# sirius1.net
KiCad netlist of a schematic drawn in EAGLE
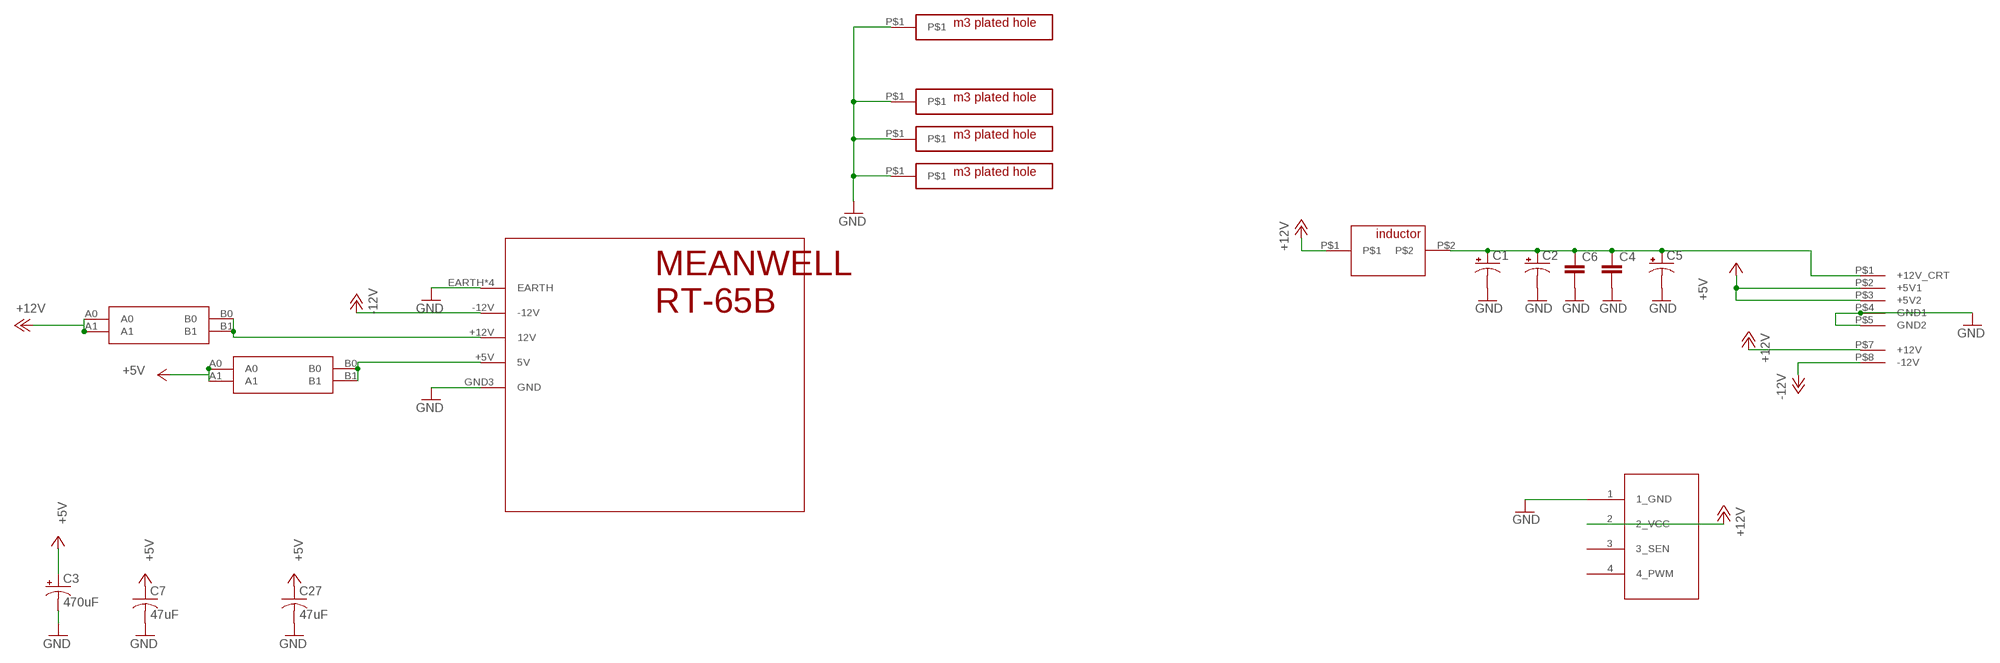
[diagram p0: schematic, sheet 1]

(export (version "E")
  (design (tool "Eeschema 10.0.6"))
  (components
    (comp (ref "C1")
      (value "CPOL-USE3.5-8")
      (footprint "eagle-import:E3,5-8")
      (libsource (lib "eagle-import") (part "CPOL-USE3.5-8"))
    )
    (comp (ref "C2")
      (value "CPOL-USE3.5-8")
      (footprint "eagle-import:E3,5-8")
      (libsource (lib "eagle-import") (part "CPOL-USE3.5-8"))
    )
    (comp (ref "C3")
      (value "470uF")
      (footprint "eagle-import:SMC_D")
      (libsource (lib "eagle-import") (part "CPOL-USSMCD"))
    )
    (comp (ref "C4")
      (value "C5/2.5")
      (footprint "eagle-import:C5B2.5")
      (libsource (lib "eagle-import") (part "C5/2.5"))
    )
    (comp (ref "C5")
      (value "CPOL-USE3.5-8")
      (footprint "eagle-import:E3,5-8")
      (libsource (lib "eagle-import") (part "CPOL-USE3.5-8"))
    )
    (comp (ref "C6")
      (value "C5/2.5")
      (footprint "eagle-import:C5B2.5")
      (libsource (lib "eagle-import") (part "C5/2.5"))
    )
    (comp (ref "C7")
      (value "47uF")
      (footprint "eagle-import:C1210")
      (libsource (lib "eagle-import") (part "C-USC1210"))
    )
    (comp (ref "C27")
      (value "47uF")
      (footprint "eagle-import:C1210")
      (libsource (lib "eagle-import") (part "C-USC1210"))
    )
    (comp (ref "JP4")
      (value "4PIN_FAN")
      (footprint "eagle-import:1X04")
      (libsource (lib "eagle-import") (part "4PIN_FAN"))
    )
    (comp (ref "U$1")
      (value "M3_HOLE_PLATEDM3")
      (footprint "eagle-import:M3_HOLE_PLATED")
      (libsource (lib "eagle-import") (part "M3_HOLE_PLATEDM3"))
    )
    (comp (ref "U$2")
      (value "M3_HOLE_PLATEDM3")
      (footprint "eagle-import:M3_HOLE_PLATED")
      (libsource (lib "eagle-import") (part "M3_HOLE_PLATEDM3"))
    )
    (comp (ref "U$4")
      (value "M3_HOLE_PLATEDM3")
      (footprint "eagle-import:M3_HOLE_PLATED")
      (libsource (lib "eagle-import") (part "M3_HOLE_PLATEDM3"))
    )
    (comp (ref "U$5")
      (value "M3_HOLE_PLATEDM3")
      (footprint "eagle-import:M3_HOLE_PLATED")
      (libsource (lib "eagle-import") (part "M3_HOLE_PLATEDM3"))
    )
    (comp (ref "U$6")
      (value "396_SIRIUS1")
      (footprint "eagle-import:396_SIRIUS1")
      (libsource (lib "eagle-import") (part "396_SIRIUS1"))
    )
    (comp (ref "U$7")
      (value "MEANWELL_RT65")
      (footprint "eagle-import:MEANWELL_RT65")
      (libsource (lib "eagle-import") (part "MEANWELL_RT65"))
    )
    (comp (ref "U$8")
      (value "CAR_FUSE_HOLDER3IN1")
      (footprint "eagle-import:FUSE_HOLDER_3IN1")
      (libsource (lib "eagle-import") (part "CAR_FUSE_HOLDER3IN1"))
    )
    (comp (ref "U$9")
      (value "CAR_FUSE_HOLDER3IN1")
      (footprint "eagle-import:FUSE_HOLDER_3IN1")
      (libsource (lib "eagle-import") (part "CAR_FUSE_HOLDER3IN1"))
    )
    (comp (ref "U$10")
      (value "INDUCTOR_PTH_8MM")
      (footprint "eagle-import:INDUCTOR_PTH_8MM")
      (libsource (lib "eagle-import") (part "INDUCTOR_PTH_8MM"))
    )
  )
  (nets
    (net (code "1") (name "+5V") (class "Default")
      (node (ref "C27") (pin "1") (pinfunction "1_1") (pintype "passive"))
      (node (ref "C3") (pin "+") (pinfunction "+_+") (pintype "passive"))
      (node (ref "C7") (pin "1") (pinfunction "1_1") (pintype "passive"))
      (node (ref "U$6") (pin "P$2") (pinfunction "+5V1_P$2") (pintype "bidirectional"))
      (node (ref "U$6") (pin "P$3") (pinfunction "+5V2_P$3") (pintype "bidirectional"))
      (node (ref "U$8") (pin "A0") (pinfunction "A0_A0") (pintype "bidirectional"))
      (node (ref "U$8") (pin "A1") (pinfunction "A1_A1") (pintype "bidirectional"))
    )
    (net (code "2") (name "+12V") (class "Default")
      (node (ref "JP4") (pin "2") (pinfunction "2_VCC_2") (pintype "passive"))
      (node (ref "U$10") (pin "P$1") (pinfunction "P$1_P$1") (pintype "bidirectional"))
      (node (ref "U$6") (pin "P$7") (pinfunction "+12V_P$7") (pintype "bidirectional"))
      (node (ref "U$9") (pin "A0") (pinfunction "A0_A0") (pintype "bidirectional"))
      (node (ref "U$9") (pin "A1") (pinfunction "A1_A1") (pintype "bidirectional"))
    )
    (net (code "3") (name "-12V") (class "Default")
      (node (ref "U$6") (pin "P$8") (pinfunction "-12V_P$8") (pintype "bidirectional"))
      (node (ref "U$7") (pin "-12V") (pinfunction "-12V_-12V") (pintype "bidirectional"))
    )
    (net (code "4") (name "GND") (class "Default")
      (node (ref "C1") (pin "-") (pinfunction "-_-") (pintype "passive"))
      (node (ref "C2") (pin "-") (pinfunction "-_-") (pintype "passive"))
      (node (ref "C27") (pin "2") (pinfunction "2_2") (pintype "passive"))
      (node (ref "C3") (pin "-") (pinfunction "-_-") (pintype "passive"))
      (node (ref "C4") (pin "2") (pinfunction "2_2") (pintype "passive"))
      (node (ref "C5") (pin "-") (pinfunction "-_-") (pintype "passive"))
      (node (ref "C6") (pin "2") (pinfunction "2_2") (pintype "passive"))
      (node (ref "C7") (pin "2") (pinfunction "2_2") (pintype "passive"))
      (node (ref "JP4") (pin "1") (pinfunction "1_GND_1") (pintype "passive"))
      (node (ref "U$1") (pin "P$1") (pinfunction "P$1_P$1") (pintype "bidirectional"))
      (node (ref "U$2") (pin "P$1") (pinfunction "P$1_P$1") (pintype "bidirectional"))
      (node (ref "U$4") (pin "P$1") (pinfunction "P$1_P$1") (pintype "bidirectional"))
      (node (ref "U$5") (pin "P$1") (pinfunction "P$1_P$1") (pintype "bidirectional"))
      (node (ref "U$6") (pin "P$4") (pinfunction "GND1_P$4") (pintype "bidirectional"))
      (node (ref "U$6") (pin "P$5") (pinfunction "GND2_P$5") (pintype "bidirectional"))
      (node (ref "U$7") (pin "EARTH") (pinfunction "EARTH_EARTH") (pintype "bidirectional"))
      (node (ref "U$7") (pin "GND") (pinfunction "EARTH_GND") (pintype "bidirectional"))
      (node (ref "U$7") (pin "GND1") (pinfunction "EARTH_GND1") (pintype "bidirectional"))
      (node (ref "U$7") (pin "GND2") (pinfunction "EARTH_GND2") (pintype "bidirectional"))
      (node (ref "U$7") (pin "GND3") (pinfunction "GND_GND3") (pintype "bidirectional"))
    )
    (net (code "5") (name "Net-(U$6-+12V_CRT)") (class "Default")
      (node (ref "C1") (pin "+") (pinfunction "+_+") (pintype "passive"))
      (node (ref "C2") (pin "+") (pinfunction "+_+") (pintype "passive"))
      (node (ref "C4") (pin "1") (pinfunction "1_1") (pintype "passive"))
      (node (ref "C5") (pin "+") (pinfunction "+_+") (pintype "passive"))
      (node (ref "C6") (pin "1") (pinfunction "1_1") (pintype "passive"))
      (node (ref "U$10") (pin "P$2") (pinfunction "P$2_P$2") (pintype "bidirectional"))
      (node (ref "U$6") (pin "P$1") (pinfunction "+12V_CRT_P$1") (pintype "bidirectional"))
    )
    (net (code "6") (name "Net-(U$7-5V)") (class "Default")
      (node (ref "U$7") (pin "+5V") (pinfunction "5V_+5V") (pintype "bidirectional"))
      (node (ref "U$8") (pin "B0") (pinfunction "B0_B0") (pintype "bidirectional"))
      (node (ref "U$8") (pin "B1") (pinfunction "B1_B1") (pintype "bidirectional"))
    )
    (net (code "7") (name "Net-(U$7-12V)") (class "Default")
      (node (ref "U$7") (pin "+12V") (pinfunction "12V_+12V") (pintype "bidirectional"))
      (node (ref "U$9") (pin "B0") (pinfunction "B0_B0") (pintype "bidirectional"))
      (node (ref "U$9") (pin "B1") (pinfunction "B1_B1") (pintype "bidirectional"))
    )
    (net (code "8") (name "unconnected-(JP4-3_SEN-Pad3)") (class "Default")
      (node (ref "JP4") (pin "3") (pinfunction "3_SEN_3") (pintype "passive"))
    )
    (net (code "9") (name "unconnected-(JP4-4_PWM-Pad4)") (class "Default")
      (node (ref "JP4") (pin "4") (pinfunction "4_PWM_4") (pintype "passive"))
    )
  )
)
